# MKL05Z_1_1.net
KiCad netlist of a schematic drawn in EAGLE
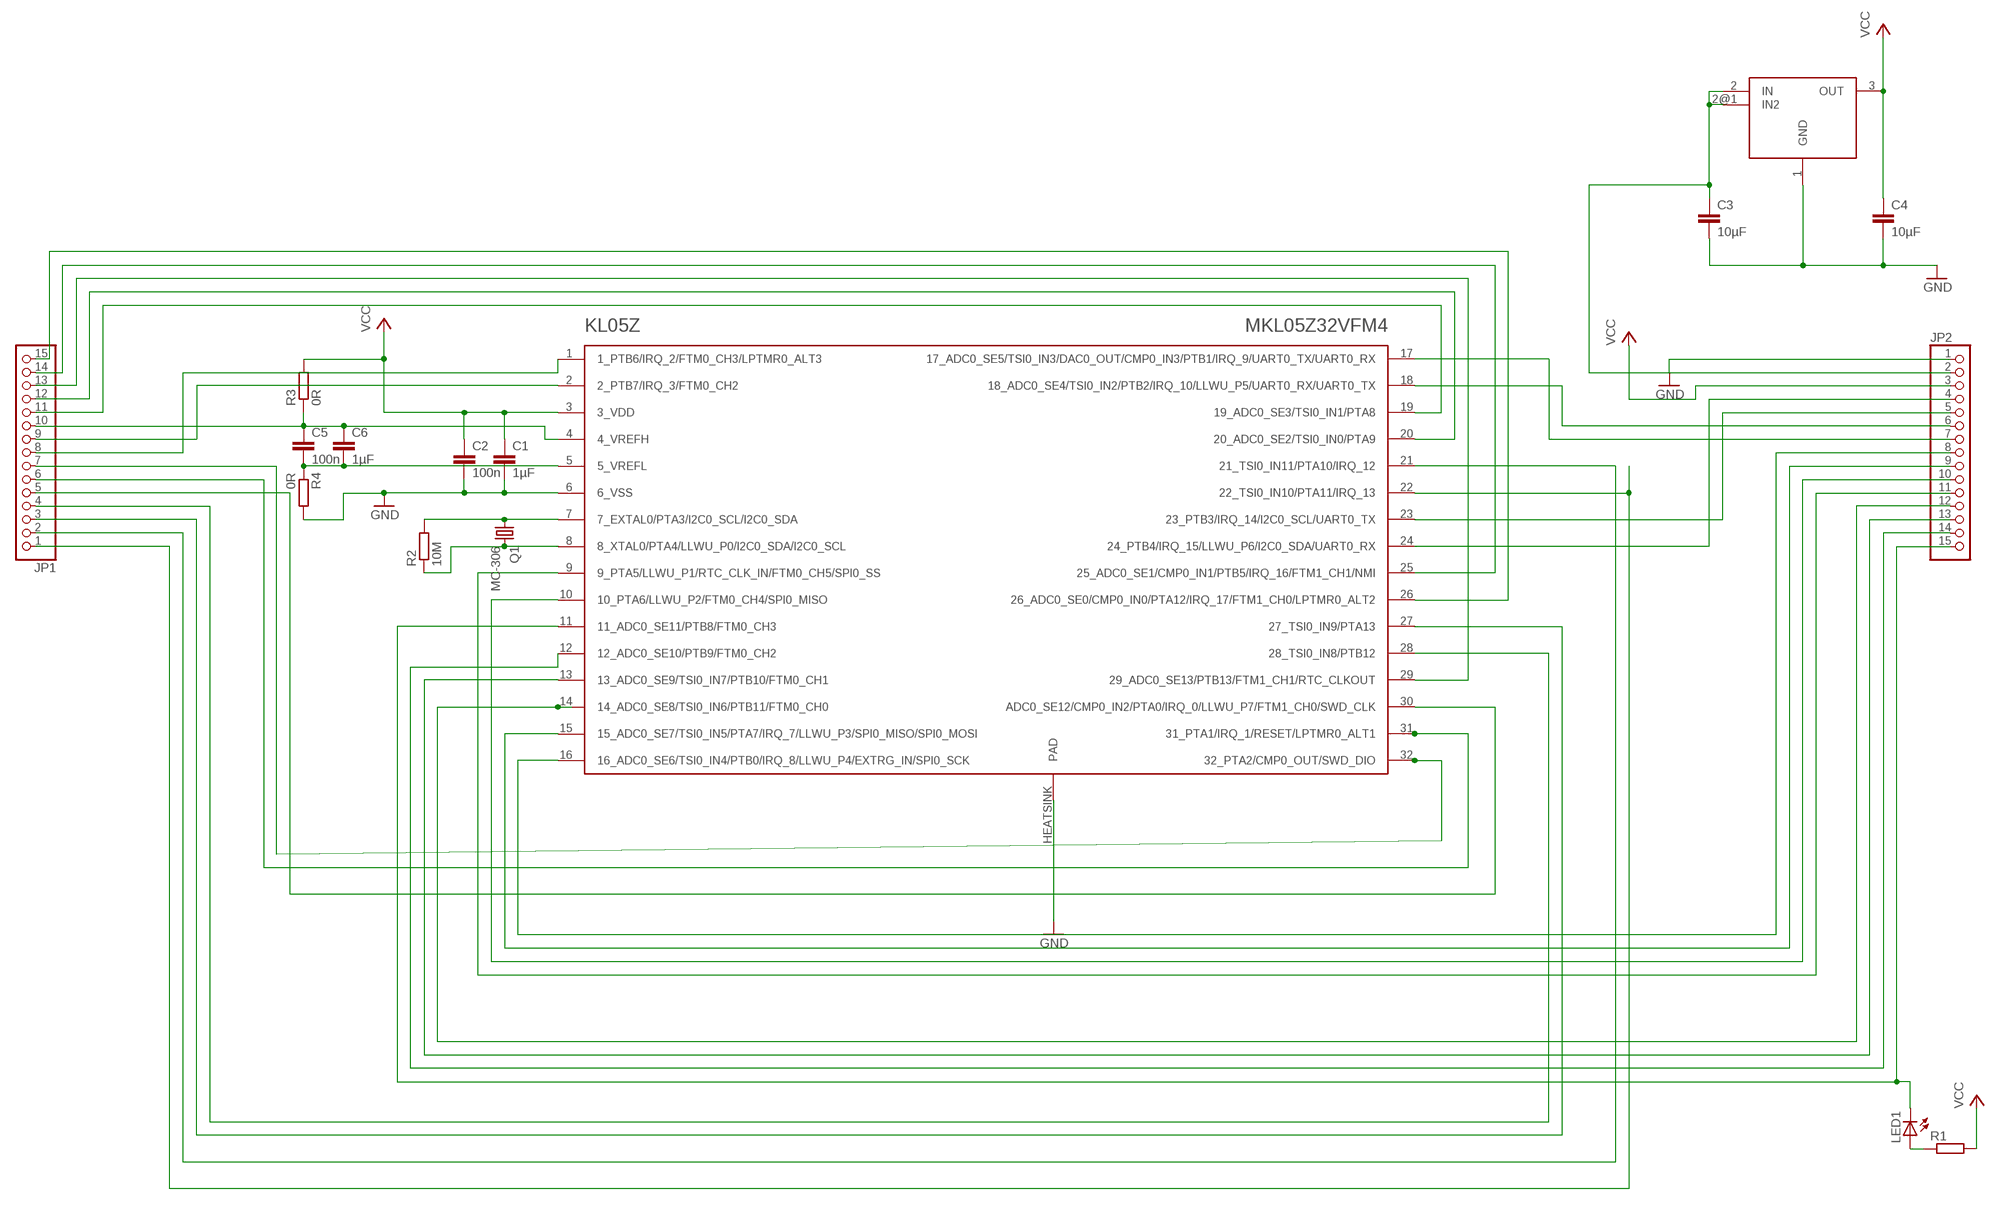
[diagram p0: schematic, sheet 1]

(export (version "E")
  (design (tool "Eeschema 10.0.6"))
  (components
    (comp (ref "C1")
      (value "1µF")
      (footprint "eagle-import:C0603")
      (libsource (lib "eagle-import") (part "C-EUC0603"))
    )
    (comp (ref "C2")
      (value "100n")
      (footprint "eagle-import:C0603")
      (libsource (lib "eagle-import") (part "C-EUC0603"))
    )
    (comp (ref "C3")
      (value "10µF")
      (footprint "eagle-import:C0805")
      (libsource (lib "eagle-import") (part "C-EUC0805"))
    )
    (comp (ref "C4")
      (value "10µF")
      (footprint "eagle-import:C0805")
      (libsource (lib "eagle-import") (part "C-EUC0805"))
    )
    (comp (ref "C5")
      (value "100n")
      (footprint "eagle-import:C0603")
      (libsource (lib "eagle-import") (part "C-EUC0603"))
    )
    (comp (ref "C6")
      (value "1µF")
      (footprint "eagle-import:C0603")
      (libsource (lib "eagle-import") (part "C-EUC0603"))
    )
    (comp (ref "JP1")
      (value "PINHD-1X15")
      (footprint "eagle-import:1X15")
      (libsource (lib "eagle-import") (part "PINHD-1X15"))
    )
    (comp (ref "JP2")
      (value "PINHD-1X15")
      (footprint "eagle-import:1X15")
      (libsource (lib "eagle-import") (part "PINHD-1X15"))
    )
    (comp (ref "KL05Z")
      (value "MKL05Z32VFM4")
      (footprint "eagle-import:QFN32")
      (libsource (lib "eagle-import") (part "MKL15Z128VFM4"))
    )
    (comp (ref "LED1")
      (value "LEDCHIPLED_0805")
      (footprint "eagle-import:CHIPLED_0805")
      (libsource (lib "eagle-import") (part "LEDCHIPLED_0805"))
    )
    (comp (ref "Q1")
      (value "MC-306")
      (footprint "eagle-import:MC-306")
      (fields (field (name "MPN") "MC-306 60.0KHZ  100PPM ,12.5PF"))
      (libsource (lib "eagle-import") (part "MC-306"))
    )
    (comp (ref "R1")
      (value "R-EU_R0603")
      (footprint "eagle-import:R0603")
      (libsource (lib "eagle-import") (part "R-EU_R0603"))
    )
    (comp (ref "R2")
      (value "10M")
      (footprint "eagle-import:R0603")
      (libsource (lib "eagle-import") (part "R-EU_R0603"))
    )
    (comp (ref "R3")
      (value "0R")
      (footprint "eagle-import:R0402")
      (libsource (lib "eagle-import") (part "R-EU_R0402"))
    )
    (comp (ref "R4")
      (value "0R")
      (footprint "eagle-import:R0402")
      (libsource (lib "eagle-import") (part "R-EU_R0402"))
    )
    (comp (ref "U$1")
      (value "HT7333")
      (footprint "eagle-import:SOT89")
      (libsource (lib "eagle-import") (part "HT7333"))
    )
  )
  (nets
    (net (code "1") (name "GND") (class "Default")
      (node (ref "C1") (pin "2") (pinfunction "2_2") (pintype "passive"))
      (node (ref "C2") (pin "2") (pinfunction "2_2") (pintype "passive"))
      (node (ref "C3") (pin "2") (pinfunction "2_2") (pintype "passive"))
      (node (ref "C4") (pin "2") (pinfunction "2_2") (pintype "passive"))
      (node (ref "JP2") (pin "1") (pinfunction "1_1") (pintype "passive"))
      (node (ref "KL05Z") (pin "6") (pinfunction "6_VSS_6") (pintype "bidirectional"))
      (node (ref "KL05Z") (pin "HEATSINK") (pinfunction "PAD_HEATSINK") (pintype "bidirectional"))
      (node (ref "R4") (pin "2") (pinfunction "2_2") (pintype "passive"))
      (node (ref "U$1") (pin "1") (pinfunction "GND_1") (pintype "bidirectional"))
    )
    (net (code "2") (name "Net-(KL05Z-1_PTB6{slash}IRQ_2{slash}FTM0_CH3{slash}LPTMR0_ALT3)") (class "Default")
      (node (ref "JP1") (pin "8") (pinfunction "8_8") (pintype "passive"))
      (node (ref "KL05Z") (pin "1") (pinfunction "1_PTB6/IRQ_2/FTM0_CH3/LPTMR0_ALT3_1") (pintype "bidirectional"))
    )
    (net (code "3") (name "Net-(KL05Z-2_PTB7{slash}IRQ_3{slash}FTM0_CH2)") (class "Default")
      (node (ref "JP1") (pin "9") (pinfunction "9_9") (pintype "passive"))
      (node (ref "KL05Z") (pin "2") (pinfunction "2_PTB7/IRQ_3/FTM0_CH2_2") (pintype "bidirectional"))
    )
    (net (code "4") (name "Net-(KL05Z-4_VREFH)") (class "Default")
      (node (ref "C5") (pin "1") (pinfunction "1_1") (pintype "passive"))
      (node (ref "C6") (pin "1") (pinfunction "1_1") (pintype "passive"))
      (node (ref "JP1") (pin "10") (pinfunction "10_10") (pintype "passive"))
      (node (ref "KL05Z") (pin "4") (pinfunction "4_VREFH_4") (pintype "bidirectional"))
      (node (ref "R3") (pin "1") (pinfunction "1_1") (pintype "passive"))
    )
    (net (code "5") (name "Net-(KL05Z-5_VREFL)") (class "Default")
      (node (ref "C5") (pin "2") (pinfunction "2_2") (pintype "passive"))
      (node (ref "C6") (pin "2") (pinfunction "2_2") (pintype "passive"))
      (node (ref "KL05Z") (pin "5") (pinfunction "5_VREFL_5") (pintype "bidirectional"))
      (node (ref "R4") (pin "1") (pinfunction "1_1") (pintype "passive"))
    )
    (net (code "6") (name "Net-(KL05Z-7_EXTAL0{slash}PTA3{slash}I2C0_SCL{slash}I2C0_SDA)") (class "Default")
      (node (ref "KL05Z") (pin "7") (pinfunction "7_EXTAL0/PTA3/I2C0_SCL/I2C0_SDA_7") (pintype "bidirectional"))
      (node (ref "Q1") (pin "1") (pinfunction "1_1") (pintype "passive"))
      (node (ref "R2") (pin "2") (pinfunction "2_2") (pintype "passive"))
    )
    (net (code "7") (name "Net-(KL05Z-8_XTAL0{slash}PTA4{slash}LLWU_P0{slash}I2C0_SDA{slash}I2C0_SCL)") (class "Default")
      (node (ref "KL05Z") (pin "8") (pinfunction "8_XTAL0/PTA4/LLWU_P0/I2C0_SDA/I2C0_SCL_8") (pintype "bidirectional"))
      (node (ref "Q1") (pin "4") (pinfunction "2_4") (pintype "passive"))
      (node (ref "R2") (pin "1") (pinfunction "1_1") (pintype "passive"))
    )
    (net (code "8") (name "Net-(KL05Z-9_PTA5{slash}LLWU_P1{slash}RTC_CLK_IN{slash}FTM0_CH5{slash}SPI0_SS)") (class "Default")
      (node (ref "JP2") (pin "11") (pinfunction "11_11") (pintype "passive"))
      (node (ref "KL05Z") (pin "9") (pinfunction "9_PTA5/LLWU_P1/RTC_CLK_IN/FTM0_CH5/SPI0_SS_9") (pintype "bidirectional"))
    )
    (net (code "9") (name "Net-(KL05Z-10_PTA6{slash}LLWU_P2{slash}FTM0_CH4{slash}SPI0_MISO)") (class "Default")
      (node (ref "JP2") (pin "10") (pinfunction "10_10") (pintype "passive"))
      (node (ref "KL05Z") (pin "10") (pinfunction "10_PTA6/LLWU_P2/FTM0_CH4/SPI0_MISO_10") (pintype "bidirectional"))
    )
    (net (code "10") (name "Net-(KL05Z-11_ADC0_SE11{slash}PTB8{slash}FTM0_CH3)") (class "Default")
      (node (ref "JP2") (pin "15") (pinfunction "15_15") (pintype "passive"))
      (node (ref "KL05Z") (pin "11") (pinfunction "11_ADC0_SE11/PTB8/FTM0_CH3_11") (pintype "bidirectional"))
      (node (ref "LED1") (pin "C") (pinfunction "C_C") (pintype "passive"))
    )
    (net (code "11") (name "Net-(KL05Z-12_ADC0_SE10{slash}PTB9{slash}FTM0_CH2)") (class "Default")
      (node (ref "JP2") (pin "14") (pinfunction "14_14") (pintype "passive"))
      (node (ref "KL05Z") (pin "12") (pinfunction "12_ADC0_SE10/PTB9/FTM0_CH2_12") (pintype "bidirectional"))
    )
    (net (code "12") (name "Net-(KL05Z-13_ADC0_SE9{slash}TSI0_IN7{slash}PTB10{slash}FTM0_CH1)") (class "Default")
      (node (ref "JP2") (pin "13") (pinfunction "13_13") (pintype "passive"))
      (node (ref "KL05Z") (pin "13") (pinfunction "13_ADC0_SE9/TSI0_IN7/PTB10/FTM0_CH1_13") (pintype "bidirectional"))
    )
    (net (code "13") (name "Net-(KL05Z-14_ADC0_SE8{slash}TSI0_IN6{slash}PTB11{slash}FTM0_CH0)") (class "Default")
      (node (ref "JP2") (pin "12") (pinfunction "12_12") (pintype "passive"))
      (node (ref "KL05Z") (pin "14") (pinfunction "14_ADC0_SE8/TSI0_IN6/PTB11/FTM0_CH0_14") (pintype "bidirectional"))
    )
    (net (code "14") (name "Net-(KL05Z-15_ADC0_SE7{slash}TSI0_IN5{slash}PTA7{slash}IRQ_7{slash}LLWU_P3{slash}SPI0_MISO{slash}SPI0_MOSI)") (class "Default")
      (node (ref "JP2") (pin "9") (pinfunction "9_9") (pintype "passive"))
      (node (ref "KL05Z") (pin "15") (pinfunction "15_ADC0_SE7/TSI0_IN5/PTA7/IRQ_7/LLWU_P3/SPI0_MISO/SPI0_MOSI_15") (pintype "bidirectional"))
    )
    (net (code "15") (name "Net-(KL05Z-16_ADC0_SE6{slash}TSI0_IN4{slash}PTB0{slash}IRQ_8{slash}LLWU_P4{slash}EXTRG_IN{slash}SPI0_SCK)") (class "Default")
      (node (ref "JP2") (pin "8") (pinfunction "8_8") (pintype "passive"))
      (node (ref "KL05Z") (pin "16") (pinfunction "16_ADC0_SE6/TSI0_IN4/PTB0/IRQ_8/LLWU_P4/EXTRG_IN/SPI0_SCK_16") (pintype "bidirectional"))
    )
    (net (code "16") (name "Net-(KL05Z-17_ADC0_SE5{slash}TSI0_IN3{slash}DAC0_OUT{slash}CMP0_IN3{slash}PTB1{slash}IRQ_9{slash}UART0_TX{slash}UART0_RX)") (class "Default")
      (node (ref "JP2") (pin "7") (pinfunction "7_7") (pintype "passive"))
      (node (ref "KL05Z") (pin "17") (pinfunction "17_ADC0_SE5/TSI0_IN3/DAC0_OUT/CMP0_IN3/PTB1/IRQ_9/UART0_TX/UART0_RX_17") (pintype "bidirectional"))
    )
    (net (code "17") (name "Net-(KL05Z-18_ADC0_SE4{slash}TSI0_IN2{slash}PTB2{slash}IRQ_10{slash}LLWU_P5{slash}UART0_RX{slash}UART0_TX)") (class "Default")
      (node (ref "JP2") (pin "6") (pinfunction "6_6") (pintype "passive"))
      (node (ref "KL05Z") (pin "18") (pinfunction "18_ADC0_SE4/TSI0_IN2/PTB2/IRQ_10/LLWU_P5/UART0_RX/UART0_TX_18") (pintype "bidirectional"))
    )
    (net (code "18") (name "Net-(KL05Z-19_ADC0_SE3{slash}TSI0_IN1{slash}PTA8)") (class "Default")
      (node (ref "JP1") (pin "11") (pinfunction "11_11") (pintype "passive"))
      (node (ref "KL05Z") (pin "19") (pinfunction "19_ADC0_SE3/TSI0_IN1/PTA8_19") (pintype "bidirectional"))
    )
    (net (code "19") (name "Net-(KL05Z-20_ADC0_SE2{slash}TSI0_IN0{slash}PTA9)") (class "Default")
      (node (ref "JP1") (pin "12") (pinfunction "12_12") (pintype "passive"))
      (node (ref "KL05Z") (pin "20") (pinfunction "20_ADC0_SE2/TSI0_IN0/PTA9_20") (pintype "bidirectional"))
    )
    (net (code "20") (name "Net-(KL05Z-21_TSI0_IN11{slash}PTA10{slash}IRQ_12)") (class "Default")
      (node (ref "JP1") (pin "2") (pinfunction "2_2") (pintype "passive"))
      (node (ref "KL05Z") (pin "21") (pinfunction "21_TSI0_IN11/PTA10/IRQ_12_21") (pintype "bidirectional"))
    )
    (net (code "21") (name "Net-(KL05Z-22_TSI0_IN10{slash}PTA11{slash}IRQ_13)") (class "Default")
      (node (ref "JP1") (pin "1") (pinfunction "1_1") (pintype "passive"))
      (node (ref "KL05Z") (pin "22") (pinfunction "22_TSI0_IN10/PTA11/IRQ_13_22") (pintype "bidirectional"))
    )
    (net (code "22") (name "Net-(KL05Z-23_PTB3{slash}IRQ_14{slash}I2C0_SCL{slash}UART0_TX)") (class "Default")
      (node (ref "JP2") (pin "5") (pinfunction "5_5") (pintype "passive"))
      (node (ref "KL05Z") (pin "23") (pinfunction "23_PTB3/IRQ_14/I2C0_SCL/UART0_TX_23") (pintype "bidirectional"))
    )
    (net (code "23") (name "Net-(KL05Z-24_PTB4{slash}IRQ_15{slash}LLWU_P6{slash}I2C0_SDA{slash}UART0_RX)") (class "Default")
      (node (ref "JP2") (pin "4") (pinfunction "4_4") (pintype "passive"))
      (node (ref "KL05Z") (pin "24") (pinfunction "24_PTB4/IRQ_15/LLWU_P6/I2C0_SDA/UART0_RX_24") (pintype "bidirectional"))
    )
    (net (code "24") (name "Net-(KL05Z-25_ADC0_SE1{slash}CMP0_IN1{slash}PTB5{slash}IRQ_16{slash}FTM1_CH1{slash}NMI)") (class "Default")
      (node (ref "JP1") (pin "14") (pinfunction "14_14") (pintype "passive"))
      (node (ref "KL05Z") (pin "25") (pinfunction "25_ADC0_SE1/CMP0_IN1/PTB5/IRQ_16/FTM1_CH1/NMI_25") (pintype "bidirectional"))
    )
    (net (code "25") (name "Net-(KL05Z-26_ADC0_SE0{slash}CMP0_IN0{slash}PTA12{slash}IRQ_17{slash}FTM1_CH0{slash}LPTMR0_ALT2)") (class "Default")
      (node (ref "JP1") (pin "15") (pinfunction "15_15") (pintype "passive"))
      (node (ref "KL05Z") (pin "26") (pinfunction "26_ADC0_SE0/CMP0_IN0/PTA12/IRQ_17/FTM1_CH0/LPTMR0_ALT2_26") (pintype "bidirectional"))
    )
    (net (code "26") (name "Net-(KL05Z-27_TSI0_IN9{slash}PTA13)") (class "Default")
      (node (ref "JP1") (pin "3") (pinfunction "3_3") (pintype "passive"))
      (node (ref "KL05Z") (pin "27") (pinfunction "27_TSI0_IN9/PTA13_27") (pintype "bidirectional"))
    )
    (net (code "27") (name "Net-(KL05Z-28_TSI0_IN8{slash}PTB12)") (class "Default")
      (node (ref "JP1") (pin "4") (pinfunction "4_4") (pintype "passive"))
      (node (ref "KL05Z") (pin "28") (pinfunction "28_TSI0_IN8/PTB12_28") (pintype "bidirectional"))
    )
    (net (code "28") (name "Net-(KL05Z-29_ADC0_SE13{slash}PTB13{slash}FTM1_CH1{slash}RTC_CLKOUT)") (class "Default")
      (node (ref "JP1") (pin "13") (pinfunction "13_13") (pintype "passive"))
      (node (ref "KL05Z") (pin "29") (pinfunction "29_ADC0_SE13/PTB13/FTM1_CH1/RTC_CLKOUT_29") (pintype "bidirectional"))
    )
    (net (code "29") (name "Net-(KL05Z-31_PTA1{slash}IRQ_1{slash}RESET{slash}LPTMR0_ALT1)") (class "Default")
      (node (ref "JP1") (pin "6") (pinfunction "6_6") (pintype "passive"))
      (node (ref "KL05Z") (pin "31") (pinfunction "31_PTA1/IRQ_1/RESET/LPTMR0_ALT1_31") (pintype "bidirectional"))
    )
    (net (code "30") (name "Net-(KL05Z-32_PTA2{slash}CMP0_OUT{slash}SWD_DIO)") (class "Default")
      (node (ref "JP1") (pin "7") (pinfunction "7_7") (pintype "passive"))
      (node (ref "KL05Z") (pin "32") (pinfunction "32_PTA2/CMP0_OUT/SWD_DIO_32") (pintype "bidirectional"))
    )
    (net (code "31") (name "Net-(KL05Z-ADC0_SE12{slash}CMP0_IN2{slash}PTA0{slash}IRQ_0{slash}LLWU_P7{slash}FTM1_CH0{slash}SWD_CLK)") (class "Default")
      (node (ref "JP1") (pin "5") (pinfunction "5_5") (pintype "passive"))
      (node (ref "KL05Z") (pin "30") (pinfunction "ADC0_SE12/CMP0_IN2/PTA0/IRQ_0/LLWU_P7/FTM1_CH0/SWD_CLK_30") (pintype "bidirectional"))
    )
    (net (code "32") (name "Net-(LED1-PadA)") (class "Default")
      (node (ref "LED1") (pin "A") (pinfunction "A_A") (pintype "passive"))
      (node (ref "R1") (pin "1") (pinfunction "1_1") (pintype "passive"))
    )
    (net (code "33") (name "Net-(U$1-IN)") (class "Default")
      (node (ref "C3") (pin "1") (pinfunction "1_1") (pintype "passive"))
      (node (ref "JP2") (pin "2") (pinfunction "2_2") (pintype "passive"))
      (node (ref "U$1") (pin "2") (pinfunction "IN_2") (pintype "bidirectional"))
      (node (ref "U$1") (pin "2@1") (pinfunction "IN2_2@1") (pintype "bidirectional"))
    )
    (net (code "34") (name "VCC") (class "Default")
      (node (ref "C1") (pin "1") (pinfunction "1_1") (pintype "passive"))
      (node (ref "C2") (pin "1") (pinfunction "1_1") (pintype "passive"))
      (node (ref "C4") (pin "1") (pinfunction "1_1") (pintype "passive"))
      (node (ref "JP2") (pin "3") (pinfunction "3_3") (pintype "passive"))
      (node (ref "KL05Z") (pin "3") (pinfunction "3_VDD_3") (pintype "bidirectional"))
      (node (ref "R1") (pin "2") (pinfunction "2_2") (pintype "passive"))
      (node (ref "R3") (pin "2") (pinfunction "2_2") (pintype "passive"))
      (node (ref "U$1") (pin "3") (pinfunction "OUT_3") (pintype "bidirectional"))
    )
  )
)
